# dirtpipe-UNO-shield-v1.net
KiCad netlist of a schematic drawn in EAGLE
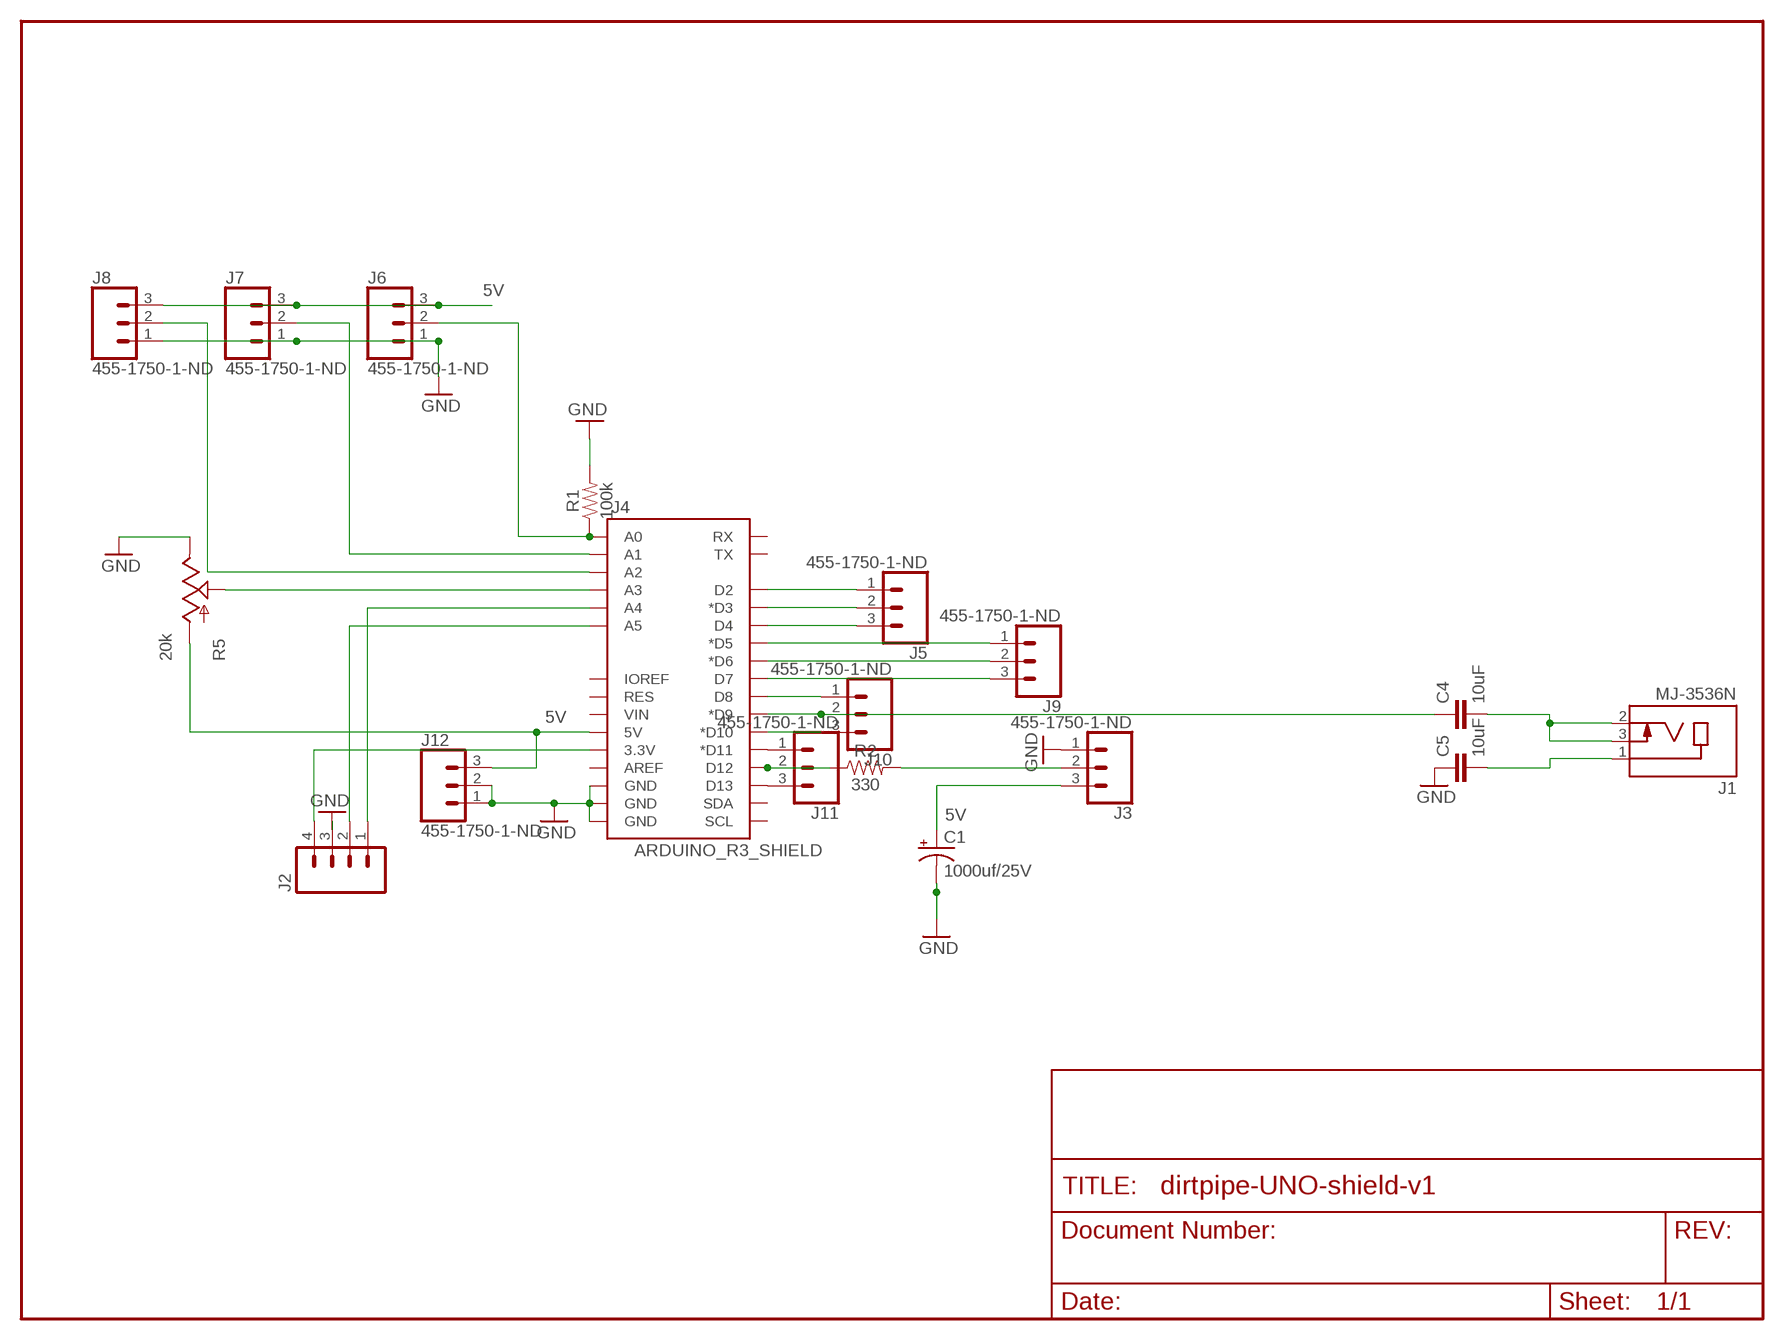
[diagram p0: schematic, sheet 1]

(export (version "E")
  (design (tool "Eeschema 10.0.6"))
  (components
    (comp (ref "C1")
      (value "1000uf/25V")
      (footprint "eagle-import:CPOL-RADIAL-1000UF-25V-KIT")
      (libsource (lib "eagle-import") (part "1000UF-25V(PTH)KIT"))
    )
    (comp (ref "C4")
      (value "10uF")
      (footprint "eagle-import:CAP-PTH-SMALL-KIT")
      (libsource (lib "eagle-import") (part "0.1UF-KIT-EZ-50V-20%"))
    )
    (comp (ref "C5")
      (value "10uF")
      (footprint "eagle-import:CAP-PTH-SMALL-KIT")
      (libsource (lib "eagle-import") (part "0.1UF-KIT-EZ-50V-20%"))
    )
    (comp (ref "J1")
      (value "MJ-3536N")
      (footprint "eagle-import:CUI_MJ-3536N")
      (fields (field (name "MANUFACTURER") "CUI INC"))
      (libsource (lib "eagle-import") (part "MJ-3536N"))
    )
    (comp (ref "J2")
      (value "M04PTH")
      (footprint "eagle-import:1X04")
      (libsource (lib "eagle-import") (part "M04PTH"))
    )
    (comp (ref "J3")
      (value "455-1750-1-ND")
      (footprint "eagle-import:1X03")
      (libsource (lib "eagle-import") (part "CONN_03"))
    )
    (comp (ref "J4")
      (value "ARDUINO_R3_SHIELD")
      (footprint "eagle-import:UNO_R3_SHIELD")
      (libsource (lib "eagle-import") (part "ARDUINO_R3_SHIELD"))
    )
    (comp (ref "J5")
      (value "455-1750-1-ND")
      (footprint "eagle-import:1X03")
      (libsource (lib "eagle-import") (part "CONN_03"))
    )
    (comp (ref "J6")
      (value "455-1750-1-ND")
      (footprint "eagle-import:1X03")
      (libsource (lib "eagle-import") (part "CONN_03"))
    )
    (comp (ref "J7")
      (value "455-1750-1-ND")
      (footprint "eagle-import:1X03")
      (libsource (lib "eagle-import") (part "CONN_03"))
    )
    (comp (ref "J8")
      (value "455-1750-1-ND")
      (footprint "eagle-import:1X03")
      (libsource (lib "eagle-import") (part "CONN_03"))
    )
    (comp (ref "J9")
      (value "455-1750-1-ND")
      (footprint "eagle-import:1X03")
      (libsource (lib "eagle-import") (part "CONN_03"))
    )
    (comp (ref "J10")
      (value "455-1750-1-ND")
      (footprint "eagle-import:1X03")
      (libsource (lib "eagle-import") (part "CONN_03"))
    )
    (comp (ref "J11")
      (value "455-1750-1-ND")
      (footprint "eagle-import:1X03")
      (libsource (lib "eagle-import") (part "CONN_03"))
    )
    (comp (ref "J12")
      (value "455-1750-1-ND")
      (footprint "eagle-import:1X03")
      (libsource (lib "eagle-import") (part "CONN_03"))
    )
    (comp (ref "R1")
      (value "100k")
      (footprint "eagle-import:AXIAL-0.3")
      (libsource (lib "eagle-import") (part "100KOHM-HORIZ-1/4W-1%"))
    )
    (comp (ref "R2")
      (value "330")
      (footprint "eagle-import:AXIAL-0.3")
      (libsource (lib "eagle-import") (part "330OHM-HORIZ-1/10W-5%"))
    )
    (comp (ref "R5")
      (value "20k")
      (footprint "eagle-import:ALPS_POT_KIT")
      (libsource (lib "eagle-import") (part "POTALPS-KIT"))
    )
  )
  (nets
    (net (code "1") (name "/5V") (class "Default")
      (node (ref "C1") (pin "+") (pinfunction "+_+") (pintype "passive"))
      (node (ref "J12") (pin "3") (pinfunction "3_3") (pintype "passive"))
      (node (ref "J3") (pin "3") (pinfunction "3_3") (pintype "passive"))
      (node (ref "J4") (pin "5V") (pinfunction "5V_5V") (pintype "bidirectional"))
      (node (ref "J6") (pin "3") (pinfunction "3_3") (pintype "passive"))
      (node (ref "J7") (pin "3") (pinfunction "3_3") (pintype "passive"))
      (node (ref "J8") (pin "3") (pinfunction "3_3") (pintype "passive"))
      (node (ref "R5") (pin "P$3") (pinfunction "A_P$3") (pintype "passive"))
    )
    (net (code "2") (name "GND") (class "Default")
      (node (ref "C1") (pin "-") (pinfunction "-_-") (pintype "passive"))
      (node (ref "C5") (pin "1") (pinfunction "1_1") (pintype "passive"))
      (node (ref "J12") (pin "1") (pinfunction "1_1") (pintype "passive"))
      (node (ref "J12") (pin "2") (pinfunction "2_2") (pintype "passive"))
      (node (ref "J2") (pin "3") (pinfunction "3_3") (pintype "passive"))
      (node (ref "J3") (pin "1") (pinfunction "1_1") (pintype "passive"))
      (node (ref "J4") (pin "GND@0") (pinfunction "GND_GND@0") (pintype "bidirectional"))
      (node (ref "J4") (pin "GND@1") (pinfunction "GND_GND@1") (pintype "bidirectional"))
      (node (ref "J4") (pin "GND@2") (pinfunction "GND_GND@2") (pintype "bidirectional"))
      (node (ref "J6") (pin "1") (pinfunction "1_1") (pintype "passive"))
      (node (ref "J7") (pin "1") (pinfunction "1_1") (pintype "passive"))
      (node (ref "J8") (pin "1") (pinfunction "1_1") (pintype "passive"))
      (node (ref "R1") (pin "P$2") (pinfunction "2_P$2") (pintype "passive"))
      (node (ref "R5") (pin "P$1") (pinfunction "E_P$1") (pintype "passive"))
    )
    (net (code "3") (name "Net-(C4-Pad2)") (class "Default")
      (node (ref "C4") (pin "2") (pinfunction "2_2") (pintype "passive"))
      (node (ref "J1") (pin "2") (pinfunction "2_2") (pintype "passive"))
      (node (ref "J1") (pin "3") (pinfunction "3_3") (pintype "passive"))
    )
    (net (code "4") (name "Net-(C5-Pad2)") (class "Default")
      (node (ref "C5") (pin "2") (pinfunction "2_2") (pintype "passive"))
      (node (ref "J1") (pin "1") (pinfunction "1_1") (pintype "passive"))
    )
    (net (code "5") (name "Net-(J2-Pad1)") (class "Default")
      (node (ref "J2") (pin "1") (pinfunction "1_1") (pintype "passive"))
      (node (ref "J4") (pin "A4") (pinfunction "A4_A4") (pintype "bidirectional"))
    )
    (net (code "6") (name "Net-(J2-Pad2)") (class "Default")
      (node (ref "J2") (pin "2") (pinfunction "2_2") (pintype "passive"))
      (node (ref "J4") (pin "A5") (pinfunction "A5_A5") (pintype "bidirectional"))
    )
    (net (code "7") (name "Net-(J2-Pad4)") (class "Default")
      (node (ref "J2") (pin "4") (pinfunction "4_4") (pintype "passive"))
      (node (ref "J4") (pin "3.3V") (pinfunction "3.3V_3.3V") (pintype "bidirectional"))
    )
    (net (code "8") (name "Net-(J4-*D3)") (class "Default")
      (node (ref "J4") (pin "D3") (pinfunction "*D3_D3") (pintype "bidirectional"))
      (node (ref "J5") (pin "2") (pinfunction "2_2") (pintype "passive"))
    )
    (net (code "9") (name "Net-(J4-*D5)") (class "Default")
      (node (ref "J4") (pin "D5") (pinfunction "*D5_D5") (pintype "bidirectional"))
      (node (ref "J9") (pin "1") (pinfunction "1_1") (pintype "passive"))
    )
    (net (code "10") (name "Net-(J4-*D6)") (class "Default")
      (node (ref "J4") (pin "D6") (pinfunction "*D6_D6") (pintype "bidirectional"))
      (node (ref "J9") (pin "2") (pinfunction "2_2") (pintype "passive"))
    )
    (net (code "11") (name "Net-(J4-*D9)") (class "Default")
      (node (ref "C4") (pin "1") (pinfunction "1_1") (pintype "passive"))
      (node (ref "J10") (pin "2") (pinfunction "2_2") (pintype "passive"))
      (node (ref "J4") (pin "D9") (pinfunction "*D9_D9") (pintype "bidirectional"))
    )
    (net (code "12") (name "Net-(J4-*D10)") (class "Default")
      (node (ref "J10") (pin "3") (pinfunction "3_3") (pintype "passive"))
      (node (ref "J4") (pin "D10") (pinfunction "*D10_D10") (pintype "bidirectional"))
    )
    (net (code "13") (name "Net-(J4-*D11)") (class "Default")
      (node (ref "J11") (pin "1") (pinfunction "1_1") (pintype "passive"))
      (node (ref "J4") (pin "D11") (pinfunction "*D11_D11") (pintype "bidirectional"))
    )
    (net (code "14") (name "Net-(J4-PadA1)") (class "Default")
      (node (ref "J4") (pin "A1") (pinfunction "A1_A1") (pintype "bidirectional"))
      (node (ref "J7") (pin "2") (pinfunction "2_2") (pintype "passive"))
    )
    (net (code "15") (name "Net-(J4-PadA2)") (class "Default")
      (node (ref "J4") (pin "A2") (pinfunction "A2_A2") (pintype "bidirectional"))
      (node (ref "J8") (pin "2") (pinfunction "2_2") (pintype "passive"))
    )
    (net (code "16") (name "Net-(J4-PadD2)") (class "Default")
      (node (ref "J4") (pin "D2") (pinfunction "D2_D2") (pintype "bidirectional"))
      (node (ref "J5") (pin "1") (pinfunction "1_1") (pintype "passive"))
    )
    (net (code "17") (name "Net-(J4-PadD4)") (class "Default")
      (node (ref "J4") (pin "D4") (pinfunction "D4_D4") (pintype "bidirectional"))
      (node (ref "J5") (pin "3") (pinfunction "3_3") (pintype "passive"))
    )
    (net (code "18") (name "Net-(J4-PadD7)") (class "Default")
      (node (ref "J4") (pin "D7") (pinfunction "D7_D7") (pintype "bidirectional"))
      (node (ref "J9") (pin "3") (pinfunction "3_3") (pintype "passive"))
    )
    (net (code "19") (name "Net-(J10-Pad1)") (class "Default")
      (node (ref "J10") (pin "1") (pinfunction "1_1") (pintype "passive"))
      (node (ref "J4") (pin "D8") (pinfunction "D8_D8") (pintype "bidirectional"))
    )
    (net (code "20") (name "Net-(J11-Pad3)") (class "Default")
      (node (ref "J11") (pin "3") (pinfunction "3_3") (pintype "passive"))
      (node (ref "J4") (pin "D13") (pinfunction "D13_D13") (pintype "bidirectional"))
    )
    (net (code "21") (name "Net-(R1-1)") (class "Default")
      (node (ref "J4") (pin "A0") (pinfunction "A0_A0") (pintype "bidirectional"))
      (node (ref "J6") (pin "2") (pinfunction "2_2") (pintype "passive"))
      (node (ref "R1") (pin "P$1") (pinfunction "1_P$1") (pintype "passive"))
    )
    (net (code "22") (name "Net-(R2-1)") (class "Default")
      (node (ref "J11") (pin "2") (pinfunction "2_2") (pintype "passive"))
      (node (ref "J4") (pin "D12") (pinfunction "D12_D12") (pintype "bidirectional"))
      (node (ref "R2") (pin "P$1") (pinfunction "1_P$1") (pintype "passive"))
    )
    (net (code "23") (name "Net-(R2-2)") (class "Default")
      (node (ref "J3") (pin "2") (pinfunction "2_2") (pintype "passive"))
      (node (ref "R2") (pin "P$2") (pinfunction "2_P$2") (pintype "passive"))
    )
    (net (code "24") (name "Net-(R5-S)") (class "Default")
      (node (ref "J4") (pin "A3") (pinfunction "A3_A3") (pintype "bidirectional"))
      (node (ref "R5") (pin "P$2") (pinfunction "S_P$2") (pintype "passive"))
    )
    (net (code "25") (name "unconnected-(J4-PadAREF)") (class "Default")
      (node (ref "J4") (pin "AREF") (pinfunction "AREF_AREF") (pintype "bidirectional"))
    )
    (net (code "26") (name "unconnected-(J4-PadIOREF)") (class "Default")
      (node (ref "J4") (pin "IOREF") (pinfunction "IOREF_IOREF") (pintype "bidirectional"))
    )
    (net (code "27") (name "unconnected-(J4-PadRES)") (class "Default")
      (node (ref "J4") (pin "RES") (pinfunction "RES_RES") (pintype "bidirectional"))
    )
    (net (code "28") (name "unconnected-(J4-PadRX)") (class "Default")
      (node (ref "J4") (pin "RX") (pinfunction "RX_RX") (pintype "bidirectional"))
    )
    (net (code "29") (name "unconnected-(J4-PadSCL)") (class "Default")
      (node (ref "J4") (pin "SCL") (pinfunction "SCL_SCL") (pintype "bidirectional"))
    )
    (net (code "30") (name "unconnected-(J4-PadSDA)") (class "Default")
      (node (ref "J4") (pin "SDA") (pinfunction "SDA_SDA") (pintype "bidirectional"))
    )
    (net (code "31") (name "unconnected-(J4-PadTX)") (class "Default")
      (node (ref "J4") (pin "TX") (pinfunction "TX_TX") (pintype "bidirectional"))
    )
    (net (code "32") (name "unconnected-(J4-PadVIN)") (class "Default")
      (node (ref "J4") (pin "VIN") (pinfunction "VIN_VIN") (pintype "bidirectional"))
    )
  )
)
